# Relay_Drivers.net
KiCad netlist of a schematic drawn in Altium Designer
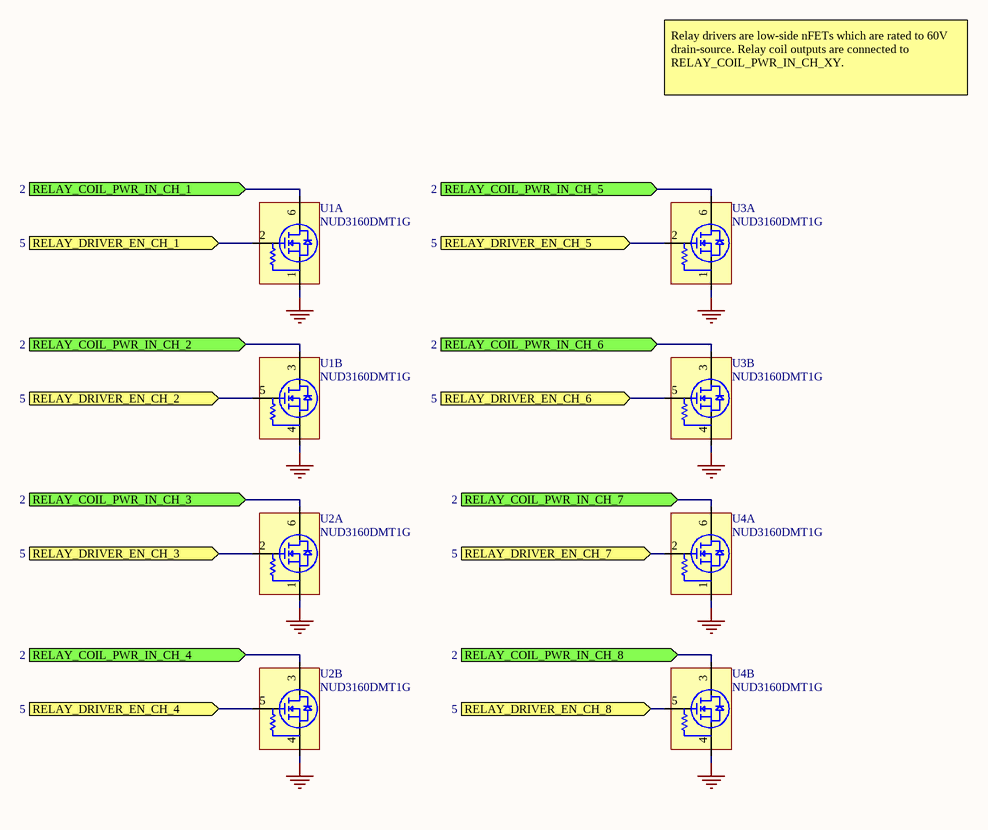
[diagram p0: Relay Drivers.SchDoc]

(export (version "E")
  (design (tool "Eeschema 10.0.6"))
  (components
    (comp (ref "U1")
      (value "NUD3160DMT1G")
      (footprint "SOT23-6")
      (description "IC INDCT LOAD DRVR INDUST SC74-6")
      (fields (field (name "MANUFACTURER") "ON Semiconductor"))
      (libsource (lib "MRT SCH Library") (part "Relay Driver Dual NUD3160DMT1G"))
    )
    (comp (ref "U2")
      (value "NUD3160DMT1G")
      (footprint "SOT23-6")
      (description "IC INDCT LOAD DRVR INDUST SC74-6")
      (fields (field (name "MANUFACTURER") "ON Semiconductor"))
      (libsource (lib "MRT SCH Library") (part "Relay Driver Dual NUD3160DMT1G"))
    )
    (comp (ref "U3")
      (value "NUD3160DMT1G")
      (footprint "SOT23-6")
      (description "IC INDCT LOAD DRVR INDUST SC74-6")
      (fields (field (name "MANUFACTURER") "ON Semiconductor"))
      (libsource (lib "MRT SCH Library") (part "Relay Driver Dual NUD3160DMT1G"))
    )
    (comp (ref "U4")
      (value "NUD3160DMT1G")
      (footprint "SOT23-6")
      (description "IC INDCT LOAD DRVR INDUST SC74-6")
      (fields (field (name "MANUFACTURER") "ON Semiconductor"))
      (libsource (lib "MRT SCH Library") (part "Relay Driver Dual NUD3160DMT1G"))
    )
  )
  (nets
    (net (code "1") (name "/RELAY_COIL_PWR_IN_CH_1") (class "Default")
      (node (ref "U1") (pin "6") (pinfunction "Drain_6") (pintype "passive"))
    )
    (net (code "2") (name "/RELAY_COIL_PWR_IN_CH_2") (class "Default")
      (node (ref "U1") (pin "3") (pinfunction "Drain_3") (pintype "passive"))
    )
    (net (code "3") (name "/RELAY_COIL_PWR_IN_CH_3") (class "Default")
      (node (ref "U2") (pin "6") (pinfunction "Drain_6") (pintype "passive"))
    )
    (net (code "4") (name "/RELAY_COIL_PWR_IN_CH_4") (class "Default")
      (node (ref "U2") (pin "3") (pinfunction "Drain_3") (pintype "passive"))
    )
    (net (code "5") (name "/RELAY_COIL_PWR_IN_CH_5") (class "Default")
      (node (ref "U3") (pin "6") (pinfunction "Drain_6") (pintype "passive"))
    )
    (net (code "6") (name "/RELAY_COIL_PWR_IN_CH_6") (class "Default")
      (node (ref "U3") (pin "3") (pinfunction "Drain_3") (pintype "passive"))
    )
    (net (code "7") (name "/RELAY_COIL_PWR_IN_CH_7") (class "Default")
      (node (ref "U4") (pin "6") (pinfunction "Drain_6") (pintype "passive"))
    )
    (net (code "8") (name "/RELAY_COIL_PWR_IN_CH_8") (class "Default")
      (node (ref "U4") (pin "3") (pinfunction "Drain_3") (pintype "passive"))
    )
    (net (code "9") (name "/RELAY_DRIVER_EN_CH_1") (class "Default")
      (node (ref "U1") (pin "2") (pinfunction "Gate_2") (pintype "passive"))
    )
    (net (code "10") (name "/RELAY_DRIVER_EN_CH_2") (class "Default")
      (node (ref "U1") (pin "5") (pinfunction "Gate_5") (pintype "passive"))
    )
    (net (code "11") (name "/RELAY_DRIVER_EN_CH_3") (class "Default")
      (node (ref "U2") (pin "2") (pinfunction "Gate_2") (pintype "passive"))
    )
    (net (code "12") (name "/RELAY_DRIVER_EN_CH_4") (class "Default")
      (node (ref "U2") (pin "5") (pinfunction "Gate_5") (pintype "passive"))
    )
    (net (code "13") (name "/RELAY_DRIVER_EN_CH_5") (class "Default")
      (node (ref "U3") (pin "2") (pinfunction "Gate_2") (pintype "passive"))
    )
    (net (code "14") (name "/RELAY_DRIVER_EN_CH_6") (class "Default")
      (node (ref "U3") (pin "5") (pinfunction "Gate_5") (pintype "passive"))
    )
    (net (code "15") (name "/RELAY_DRIVER_EN_CH_7") (class "Default")
      (node (ref "U4") (pin "2") (pinfunction "Gate_2") (pintype "passive"))
    )
    (net (code "16") (name "/RELAY_DRIVER_EN_CH_8") (class "Default")
      (node (ref "U4") (pin "5") (pinfunction "Gate_5") (pintype "passive"))
    )
    (net (code "17") (name "GND") (class "Default")
      (node (ref "U1") (pin "1") (pinfunction "Source_1") (pintype "passive"))
      (node (ref "U1") (pin "4") (pinfunction "Source_4") (pintype "passive"))
      (node (ref "U2") (pin "1") (pinfunction "Source_1") (pintype "passive"))
      (node (ref "U2") (pin "4") (pinfunction "Source_4") (pintype "passive"))
      (node (ref "U3") (pin "1") (pinfunction "Source_1") (pintype "passive"))
      (node (ref "U3") (pin "4") (pinfunction "Source_4") (pintype "passive"))
      (node (ref "U4") (pin "1") (pinfunction "Source_1") (pintype "passive"))
      (node (ref "U4") (pin "4") (pinfunction "Source_4") (pintype "passive"))
    )
  )
)
